# Sheet2.net
KiCad netlist of a schematic drawn in Altium Designer
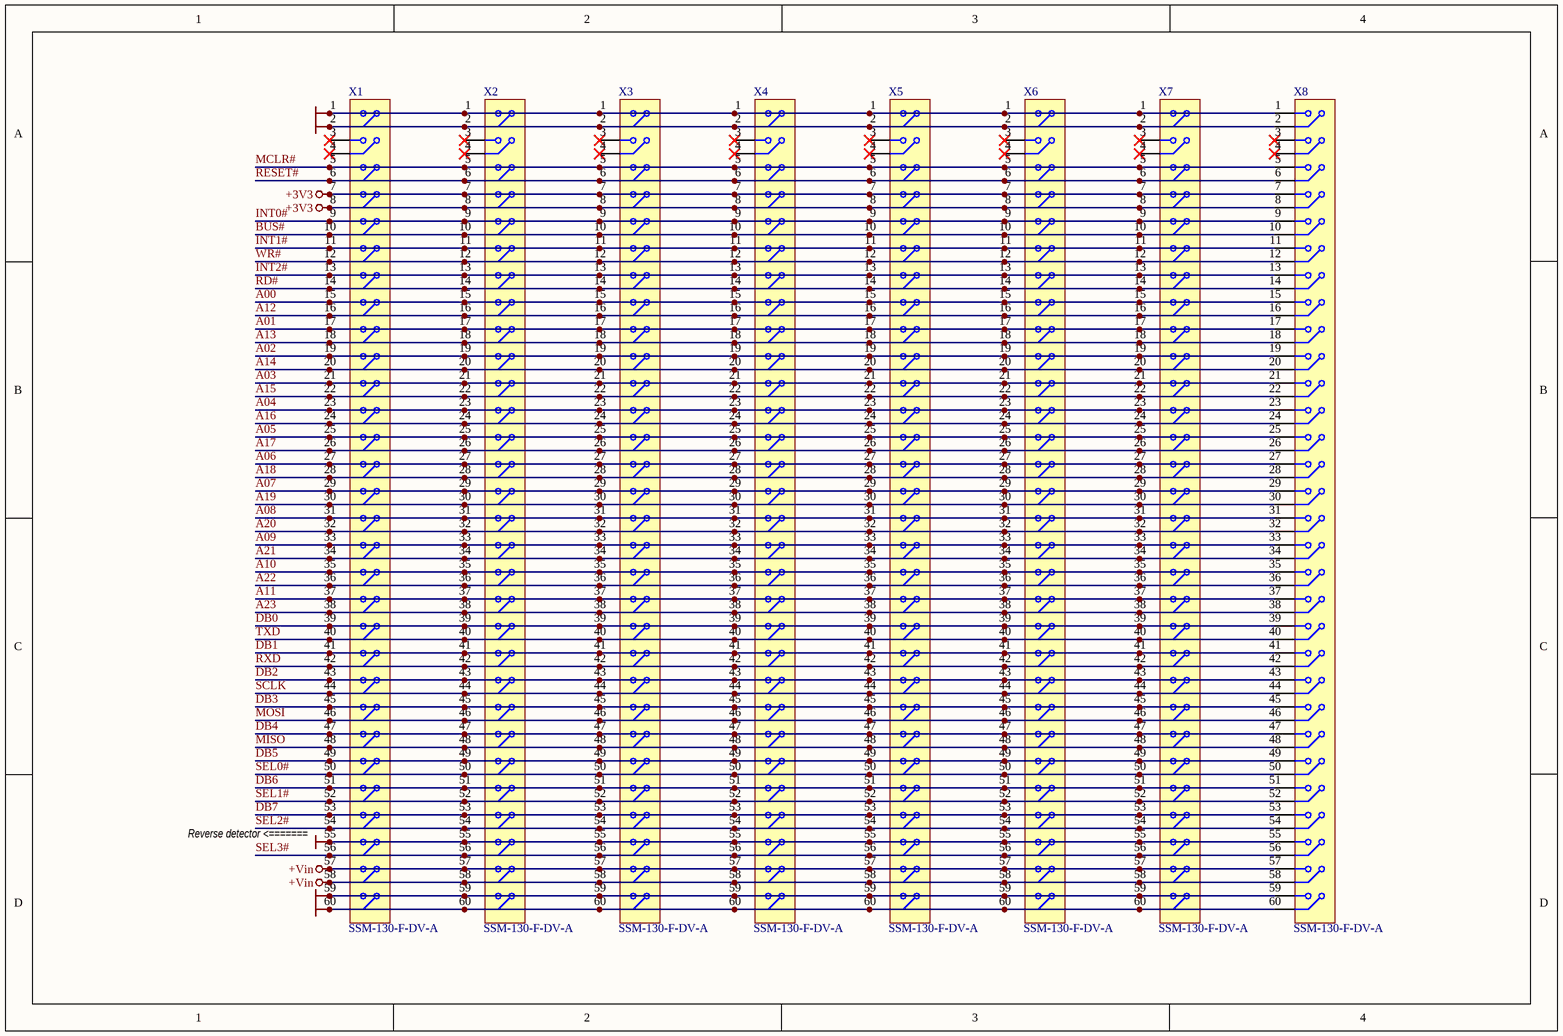
[diagram p0: Sheet2.SchDoc]

(export (version "E")
  (design (tool "Eeschema 10.0.6"))
  (components
    (comp (ref "X1")
      (value "SSM-130-F-DV-A")
      (footprint "2015-2X30XD")
      (description "Dual row, 60-way connector")
      (libsource (lib "Connectors") (part "Connector 2x30"))
    )
    (comp (ref "X2")
      (value "SSM-130-F-DV-A")
      (footprint "2015-2X30XD")
      (description "Dual row, 60-way connector")
      (libsource (lib "Connectors") (part "Connector 2x30"))
    )
    (comp (ref "X3")
      (value "SSM-130-F-DV-A")
      (footprint "2015-2X30XD")
      (description "Dual row, 60-way connector")
      (libsource (lib "Connectors") (part "Connector 2x30"))
    )
    (comp (ref "X4")
      (value "SSM-130-F-DV-A")
      (footprint "2015-2X30XD")
      (description "Dual row, 60-way connector")
      (libsource (lib "Connectors") (part "Connector 2x30"))
    )
    (comp (ref "X5")
      (value "SSM-130-F-DV-A")
      (footprint "2015-2X30XD")
      (description "Dual row, 60-way connector")
      (libsource (lib "Connectors") (part "Connector 2x30"))
    )
    (comp (ref "X6")
      (value "SSM-130-F-DV-A")
      (footprint "2015-2X30XD")
      (description "Dual row, 60-way connector")
      (libsource (lib "Connectors") (part "Connector 2x30"))
    )
    (comp (ref "X7")
      (value "SSM-130-F-DV-A")
      (footprint "2015-2X30XD")
      (description "Dual row, 60-way connector")
      (libsource (lib "Connectors") (part "Connector 2x30"))
    )
    (comp (ref "X8")
      (value "SSM-130-F-DV-A")
      (footprint "2015-2X30XD")
      (description "Dual row, 60-way connector")
      (libsource (lib "Connectors") (part "Connector 2x30"))
    )
  )
  (nets
    (net (code "1") (name "+3V3") (class "Default")
      (node (ref "X1") (pin "7") (pinfunction "7_7") (pintype "passive"))
      (node (ref "X1") (pin "8") (pinfunction "8_8") (pintype "passive"))
      (node (ref "X2") (pin "7") (pinfunction "7_7") (pintype "passive"))
      (node (ref "X2") (pin "8") (pinfunction "8_8") (pintype "passive"))
      (node (ref "X3") (pin "7") (pinfunction "7_7") (pintype "passive"))
      (node (ref "X3") (pin "8") (pinfunction "8_8") (pintype "passive"))
      (node (ref "X4") (pin "7") (pinfunction "7_7") (pintype "passive"))
      (node (ref "X4") (pin "8") (pinfunction "8_8") (pintype "passive"))
      (node (ref "X5") (pin "7") (pinfunction "7_7") (pintype "passive"))
      (node (ref "X5") (pin "8") (pinfunction "8_8") (pintype "passive"))
      (node (ref "X6") (pin "7") (pinfunction "7_7") (pintype "passive"))
      (node (ref "X6") (pin "8") (pinfunction "8_8") (pintype "passive"))
      (node (ref "X7") (pin "7") (pinfunction "7_7") (pintype "passive"))
      (node (ref "X7") (pin "8") (pinfunction "8_8") (pintype "passive"))
      (node (ref "X8") (pin "7") (pinfunction "7_7") (pintype "passive"))
      (node (ref "X8") (pin "8") (pinfunction "8_8") (pintype "passive"))
    )
    (net (code "2") (name "+Vin") (class "Default")
      (node (ref "X1") (pin "57") (pinfunction "57_57") (pintype "passive"))
      (node (ref "X1") (pin "58") (pinfunction "58_58") (pintype "passive"))
      (node (ref "X2") (pin "57") (pinfunction "57_57") (pintype "passive"))
      (node (ref "X2") (pin "58") (pinfunction "58_58") (pintype "passive"))
      (node (ref "X3") (pin "57") (pinfunction "57_57") (pintype "passive"))
      (node (ref "X3") (pin "58") (pinfunction "58_58") (pintype "passive"))
      (node (ref "X4") (pin "57") (pinfunction "57_57") (pintype "passive"))
      (node (ref "X4") (pin "58") (pinfunction "58_58") (pintype "passive"))
      (node (ref "X5") (pin "57") (pinfunction "57_57") (pintype "passive"))
      (node (ref "X5") (pin "58") (pinfunction "58_58") (pintype "passive"))
      (node (ref "X6") (pin "57") (pinfunction "57_57") (pintype "passive"))
      (node (ref "X6") (pin "58") (pinfunction "58_58") (pintype "passive"))
      (node (ref "X7") (pin "57") (pinfunction "57_57") (pintype "passive"))
      (node (ref "X7") (pin "58") (pinfunction "58_58") (pintype "passive"))
      (node (ref "X8") (pin "57") (pinfunction "57_57") (pintype "passive"))
      (node (ref "X8") (pin "58") (pinfunction "58_58") (pintype "passive"))
    )
    (net (code "3") (name "/A00") (class "Default")
      (node (ref "X1") (pin "15") (pinfunction "15_15") (pintype "passive"))
      (node (ref "X2") (pin "15") (pinfunction "15_15") (pintype "passive"))
      (node (ref "X3") (pin "15") (pinfunction "15_15") (pintype "passive"))
      (node (ref "X4") (pin "15") (pinfunction "15_15") (pintype "passive"))
      (node (ref "X5") (pin "15") (pinfunction "15_15") (pintype "passive"))
      (node (ref "X6") (pin "15") (pinfunction "15_15") (pintype "passive"))
      (node (ref "X7") (pin "15") (pinfunction "15_15") (pintype "passive"))
      (node (ref "X8") (pin "15") (pinfunction "15_15") (pintype "passive"))
    )
    (net (code "4") (name "/A01") (class "Default")
      (node (ref "X1") (pin "17") (pinfunction "17_17") (pintype "passive"))
      (node (ref "X2") (pin "17") (pinfunction "17_17") (pintype "passive"))
      (node (ref "X3") (pin "17") (pinfunction "17_17") (pintype "passive"))
      (node (ref "X4") (pin "17") (pinfunction "17_17") (pintype "passive"))
      (node (ref "X5") (pin "17") (pinfunction "17_17") (pintype "passive"))
      (node (ref "X6") (pin "17") (pinfunction "17_17") (pintype "passive"))
      (node (ref "X7") (pin "17") (pinfunction "17_17") (pintype "passive"))
      (node (ref "X8") (pin "17") (pinfunction "17_17") (pintype "passive"))
    )
    (net (code "5") (name "/A02") (class "Default")
      (node (ref "X1") (pin "19") (pinfunction "19_19") (pintype "passive"))
      (node (ref "X2") (pin "19") (pinfunction "19_19") (pintype "passive"))
      (node (ref "X3") (pin "19") (pinfunction "19_19") (pintype "passive"))
      (node (ref "X4") (pin "19") (pinfunction "19_19") (pintype "passive"))
      (node (ref "X5") (pin "19") (pinfunction "19_19") (pintype "passive"))
      (node (ref "X6") (pin "19") (pinfunction "19_19") (pintype "passive"))
      (node (ref "X7") (pin "19") (pinfunction "19_19") (pintype "passive"))
      (node (ref "X8") (pin "19") (pinfunction "19_19") (pintype "passive"))
    )
    (net (code "6") (name "/A03") (class "Default")
      (node (ref "X1") (pin "21") (pinfunction "21_21") (pintype "passive"))
      (node (ref "X2") (pin "21") (pinfunction "21_21") (pintype "passive"))
      (node (ref "X3") (pin "21") (pinfunction "21_21") (pintype "passive"))
      (node (ref "X4") (pin "21") (pinfunction "21_21") (pintype "passive"))
      (node (ref "X5") (pin "21") (pinfunction "21_21") (pintype "passive"))
      (node (ref "X6") (pin "21") (pinfunction "21_21") (pintype "passive"))
      (node (ref "X7") (pin "21") (pinfunction "21_21") (pintype "passive"))
      (node (ref "X8") (pin "21") (pinfunction "21_21") (pintype "passive"))
    )
    (net (code "7") (name "/A04") (class "Default")
      (node (ref "X1") (pin "23") (pinfunction "23_23") (pintype "passive"))
      (node (ref "X2") (pin "23") (pinfunction "23_23") (pintype "passive"))
      (node (ref "X3") (pin "23") (pinfunction "23_23") (pintype "passive"))
      (node (ref "X4") (pin "23") (pinfunction "23_23") (pintype "passive"))
      (node (ref "X5") (pin "23") (pinfunction "23_23") (pintype "passive"))
      (node (ref "X6") (pin "23") (pinfunction "23_23") (pintype "passive"))
      (node (ref "X7") (pin "23") (pinfunction "23_23") (pintype "passive"))
      (node (ref "X8") (pin "23") (pinfunction "23_23") (pintype "passive"))
    )
    (net (code "8") (name "/A05") (class "Default")
      (node (ref "X1") (pin "25") (pinfunction "25_25") (pintype "passive"))
      (node (ref "X2") (pin "25") (pinfunction "25_25") (pintype "passive"))
      (node (ref "X3") (pin "25") (pinfunction "25_25") (pintype "passive"))
      (node (ref "X4") (pin "25") (pinfunction "25_25") (pintype "passive"))
      (node (ref "X5") (pin "25") (pinfunction "25_25") (pintype "passive"))
      (node (ref "X6") (pin "25") (pinfunction "25_25") (pintype "passive"))
      (node (ref "X7") (pin "25") (pinfunction "25_25") (pintype "passive"))
      (node (ref "X8") (pin "25") (pinfunction "25_25") (pintype "passive"))
    )
    (net (code "9") (name "/A06") (class "Default")
      (node (ref "X1") (pin "27") (pinfunction "27_27") (pintype "passive"))
      (node (ref "X2") (pin "27") (pinfunction "27_27") (pintype "passive"))
      (node (ref "X3") (pin "27") (pinfunction "27_27") (pintype "passive"))
      (node (ref "X4") (pin "27") (pinfunction "27_27") (pintype "passive"))
      (node (ref "X5") (pin "27") (pinfunction "27_27") (pintype "passive"))
      (node (ref "X6") (pin "27") (pinfunction "27_27") (pintype "passive"))
      (node (ref "X7") (pin "27") (pinfunction "27_27") (pintype "passive"))
      (node (ref "X8") (pin "27") (pinfunction "27_27") (pintype "passive"))
    )
    (net (code "10") (name "/A07") (class "Default")
      (node (ref "X1") (pin "29") (pinfunction "29_29") (pintype "passive"))
      (node (ref "X2") (pin "29") (pinfunction "29_29") (pintype "passive"))
      (node (ref "X3") (pin "29") (pinfunction "29_29") (pintype "passive"))
      (node (ref "X4") (pin "29") (pinfunction "29_29") (pintype "passive"))
      (node (ref "X5") (pin "29") (pinfunction "29_29") (pintype "passive"))
      (node (ref "X6") (pin "29") (pinfunction "29_29") (pintype "passive"))
      (node (ref "X7") (pin "29") (pinfunction "29_29") (pintype "passive"))
      (node (ref "X8") (pin "29") (pinfunction "29_29") (pintype "passive"))
    )
    (net (code "11") (name "/A08") (class "Default")
      (node (ref "X1") (pin "31") (pinfunction "31_31") (pintype "passive"))
      (node (ref "X2") (pin "31") (pinfunction "31_31") (pintype "passive"))
      (node (ref "X3") (pin "31") (pinfunction "31_31") (pintype "passive"))
      (node (ref "X4") (pin "31") (pinfunction "31_31") (pintype "passive"))
      (node (ref "X5") (pin "31") (pinfunction "31_31") (pintype "passive"))
      (node (ref "X6") (pin "31") (pinfunction "31_31") (pintype "passive"))
      (node (ref "X7") (pin "31") (pinfunction "31_31") (pintype "passive"))
      (node (ref "X8") (pin "31") (pinfunction "31_31") (pintype "passive"))
    )
    (net (code "12") (name "/A09") (class "Default")
      (node (ref "X1") (pin "33") (pinfunction "33_33") (pintype "passive"))
      (node (ref "X2") (pin "33") (pinfunction "33_33") (pintype "passive"))
      (node (ref "X3") (pin "33") (pinfunction "33_33") (pintype "passive"))
      (node (ref "X4") (pin "33") (pinfunction "33_33") (pintype "passive"))
      (node (ref "X5") (pin "33") (pinfunction "33_33") (pintype "passive"))
      (node (ref "X6") (pin "33") (pinfunction "33_33") (pintype "passive"))
      (node (ref "X7") (pin "33") (pinfunction "33_33") (pintype "passive"))
      (node (ref "X8") (pin "33") (pinfunction "33_33") (pintype "passive"))
    )
    (net (code "13") (name "/A10") (class "Default")
      (node (ref "X1") (pin "35") (pinfunction "35_35") (pintype "passive"))
      (node (ref "X2") (pin "35") (pinfunction "35_35") (pintype "passive"))
      (node (ref "X3") (pin "35") (pinfunction "35_35") (pintype "passive"))
      (node (ref "X4") (pin "35") (pinfunction "35_35") (pintype "passive"))
      (node (ref "X5") (pin "35") (pinfunction "35_35") (pintype "passive"))
      (node (ref "X6") (pin "35") (pinfunction "35_35") (pintype "passive"))
      (node (ref "X7") (pin "35") (pinfunction "35_35") (pintype "passive"))
      (node (ref "X8") (pin "35") (pinfunction "35_35") (pintype "passive"))
    )
    (net (code "14") (name "/A11") (class "Default")
      (node (ref "X1") (pin "37") (pinfunction "37_37") (pintype "passive"))
      (node (ref "X2") (pin "37") (pinfunction "37_37") (pintype "passive"))
      (node (ref "X3") (pin "37") (pinfunction "37_37") (pintype "passive"))
      (node (ref "X4") (pin "37") (pinfunction "37_37") (pintype "passive"))
      (node (ref "X5") (pin "37") (pinfunction "37_37") (pintype "passive"))
      (node (ref "X6") (pin "37") (pinfunction "37_37") (pintype "passive"))
      (node (ref "X7") (pin "37") (pinfunction "37_37") (pintype "passive"))
      (node (ref "X8") (pin "37") (pinfunction "37_37") (pintype "passive"))
    )
    (net (code "15") (name "/A12") (class "Default")
      (node (ref "X1") (pin "16") (pinfunction "16_16") (pintype "passive"))
      (node (ref "X2") (pin "16") (pinfunction "16_16") (pintype "passive"))
      (node (ref "X3") (pin "16") (pinfunction "16_16") (pintype "passive"))
      (node (ref "X4") (pin "16") (pinfunction "16_16") (pintype "passive"))
      (node (ref "X5") (pin "16") (pinfunction "16_16") (pintype "passive"))
      (node (ref "X6") (pin "16") (pinfunction "16_16") (pintype "passive"))
      (node (ref "X7") (pin "16") (pinfunction "16_16") (pintype "passive"))
      (node (ref "X8") (pin "16") (pinfunction "16_16") (pintype "passive"))
    )
    (net (code "16") (name "/A13") (class "Default")
      (node (ref "X1") (pin "18") (pinfunction "18_18") (pintype "passive"))
      (node (ref "X2") (pin "18") (pinfunction "18_18") (pintype "passive"))
      (node (ref "X3") (pin "18") (pinfunction "18_18") (pintype "passive"))
      (node (ref "X4") (pin "18") (pinfunction "18_18") (pintype "passive"))
      (node (ref "X5") (pin "18") (pinfunction "18_18") (pintype "passive"))
      (node (ref "X6") (pin "18") (pinfunction "18_18") (pintype "passive"))
      (node (ref "X7") (pin "18") (pinfunction "18_18") (pintype "passive"))
      (node (ref "X8") (pin "18") (pinfunction "18_18") (pintype "passive"))
    )
    (net (code "17") (name "/A14") (class "Default")
      (node (ref "X1") (pin "20") (pinfunction "20_20") (pintype "passive"))
      (node (ref "X2") (pin "20") (pinfunction "20_20") (pintype "passive"))
      (node (ref "X3") (pin "20") (pinfunction "20_20") (pintype "passive"))
      (node (ref "X4") (pin "20") (pinfunction "20_20") (pintype "passive"))
      (node (ref "X5") (pin "20") (pinfunction "20_20") (pintype "passive"))
      (node (ref "X6") (pin "20") (pinfunction "20_20") (pintype "passive"))
      (node (ref "X7") (pin "20") (pinfunction "20_20") (pintype "passive"))
      (node (ref "X8") (pin "20") (pinfunction "20_20") (pintype "passive"))
    )
    (net (code "18") (name "/A15") (class "Default")
      (node (ref "X1") (pin "22") (pinfunction "22_22") (pintype "passive"))
      (node (ref "X2") (pin "22") (pinfunction "22_22") (pintype "passive"))
      (node (ref "X3") (pin "22") (pinfunction "22_22") (pintype "passive"))
      (node (ref "X4") (pin "22") (pinfunction "22_22") (pintype "passive"))
      (node (ref "X5") (pin "22") (pinfunction "22_22") (pintype "passive"))
      (node (ref "X6") (pin "22") (pinfunction "22_22") (pintype "passive"))
      (node (ref "X7") (pin "22") (pinfunction "22_22") (pintype "passive"))
      (node (ref "X8") (pin "22") (pinfunction "22_22") (pintype "passive"))
    )
    (net (code "19") (name "/A16") (class "Default")
      (node (ref "X1") (pin "24") (pinfunction "24_24") (pintype "passive"))
      (node (ref "X2") (pin "24") (pinfunction "24_24") (pintype "passive"))
      (node (ref "X3") (pin "24") (pinfunction "24_24") (pintype "passive"))
      (node (ref "X4") (pin "24") (pinfunction "24_24") (pintype "passive"))
      (node (ref "X5") (pin "24") (pinfunction "24_24") (pintype "passive"))
      (node (ref "X6") (pin "24") (pinfunction "24_24") (pintype "passive"))
      (node (ref "X7") (pin "24") (pinfunction "24_24") (pintype "passive"))
      (node (ref "X8") (pin "24") (pinfunction "24_24") (pintype "passive"))
    )
    (net (code "20") (name "/A17") (class "Default")
      (node (ref "X1") (pin "26") (pinfunction "26_26") (pintype "passive"))
      (node (ref "X2") (pin "26") (pinfunction "26_26") (pintype "passive"))
      (node (ref "X3") (pin "26") (pinfunction "26_26") (pintype "passive"))
      (node (ref "X4") (pin "26") (pinfunction "26_26") (pintype "passive"))
      (node (ref "X5") (pin "26") (pinfunction "26_26") (pintype "passive"))
      (node (ref "X6") (pin "26") (pinfunction "26_26") (pintype "passive"))
      (node (ref "X7") (pin "26") (pinfunction "26_26") (pintype "passive"))
      (node (ref "X8") (pin "26") (pinfunction "26_26") (pintype "passive"))
    )
    (net (code "21") (name "/A18") (class "Default")
      (node (ref "X1") (pin "28") (pinfunction "28_28") (pintype "passive"))
      (node (ref "X2") (pin "28") (pinfunction "28_28") (pintype "passive"))
      (node (ref "X3") (pin "28") (pinfunction "28_28") (pintype "passive"))
      (node (ref "X4") (pin "28") (pinfunction "28_28") (pintype "passive"))
      (node (ref "X5") (pin "28") (pinfunction "28_28") (pintype "passive"))
      (node (ref "X6") (pin "28") (pinfunction "28_28") (pintype "passive"))
      (node (ref "X7") (pin "28") (pinfunction "28_28") (pintype "passive"))
      (node (ref "X8") (pin "28") (pinfunction "28_28") (pintype "passive"))
    )
    (net (code "22") (name "/A19") (class "Default")
      (node (ref "X1") (pin "30") (pinfunction "30_30") (pintype "passive"))
      (node (ref "X2") (pin "30") (pinfunction "30_30") (pintype "passive"))
      (node (ref "X3") (pin "30") (pinfunction "30_30") (pintype "passive"))
      (node (ref "X4") (pin "30") (pinfunction "30_30") (pintype "passive"))
      (node (ref "X5") (pin "30") (pinfunction "30_30") (pintype "passive"))
      (node (ref "X6") (pin "30") (pinfunction "30_30") (pintype "passive"))
      (node (ref "X7") (pin "30") (pinfunction "30_30") (pintype "passive"))
      (node (ref "X8") (pin "30") (pinfunction "30_30") (pintype "passive"))
    )
    (net (code "23") (name "/A20") (class "Default")
      (node (ref "X1") (pin "32") (pinfunction "32_32") (pintype "passive"))
      (node (ref "X2") (pin "32") (pinfunction "32_32") (pintype "passive"))
      (node (ref "X3") (pin "32") (pinfunction "32_32") (pintype "passive"))
      (node (ref "X4") (pin "32") (pinfunction "32_32") (pintype "passive"))
      (node (ref "X5") (pin "32") (pinfunction "32_32") (pintype "passive"))
      (node (ref "X6") (pin "32") (pinfunction "32_32") (pintype "passive"))
      (node (ref "X7") (pin "32") (pinfunction "32_32") (pintype "passive"))
      (node (ref "X8") (pin "32") (pinfunction "32_32") (pintype "passive"))
    )
    (net (code "24") (name "/A21") (class "Default")
      (node (ref "X1") (pin "34") (pinfunction "34_34") (pintype "passive"))
      (node (ref "X2") (pin "34") (pinfunction "34_34") (pintype "passive"))
      (node (ref "X3") (pin "34") (pinfunction "34_34") (pintype "passive"))
      (node (ref "X4") (pin "34") (pinfunction "34_34") (pintype "passive"))
      (node (ref "X5") (pin "34") (pinfunction "34_34") (pintype "passive"))
      (node (ref "X6") (pin "34") (pinfunction "34_34") (pintype "passive"))
      (node (ref "X7") (pin "34") (pinfunction "34_34") (pintype "passive"))
      (node (ref "X8") (pin "34") (pinfunction "34_34") (pintype "passive"))
    )
    (net (code "25") (name "/A22") (class "Default")
      (node (ref "X1") (pin "36") (pinfunction "36_36") (pintype "passive"))
      (node (ref "X2") (pin "36") (pinfunction "36_36") (pintype "passive"))
      (node (ref "X3") (pin "36") (pinfunction "36_36") (pintype "passive"))
      (node (ref "X4") (pin "36") (pinfunction "36_36") (pintype "passive"))
      (node (ref "X5") (pin "36") (pinfunction "36_36") (pintype "passive"))
      (node (ref "X6") (pin "36") (pinfunction "36_36") (pintype "passive"))
      (node (ref "X7") (pin "36") (pinfunction "36_36") (pintype "passive"))
      (node (ref "X8") (pin "36") (pinfunction "36_36") (pintype "passive"))
    )
    (net (code "26") (name "/A23") (class "Default")
      (node (ref "X1") (pin "38") (pinfunction "38_38") (pintype "passive"))
      (node (ref "X2") (pin "38") (pinfunction "38_38") (pintype "passive"))
      (node (ref "X3") (pin "38") (pinfunction "38_38") (pintype "passive"))
      (node (ref "X4") (pin "38") (pinfunction "38_38") (pintype "passive"))
      (node (ref "X5") (pin "38") (pinfunction "38_38") (pintype "passive"))
      (node (ref "X6") (pin "38") (pinfunction "38_38") (pintype "passive"))
      (node (ref "X7") (pin "38") (pinfunction "38_38") (pintype "passive"))
      (node (ref "X8") (pin "38") (pinfunction "38_38") (pintype "passive"))
    )
    (net (code "27") (name "/BUS#") (class "Default")
      (node (ref "X1") (pin "10") (pinfunction "10_10") (pintype "passive"))
      (node (ref "X2") (pin "10") (pinfunction "10_10") (pintype "passive"))
      (node (ref "X3") (pin "10") (pinfunction "10_10") (pintype "passive"))
      (node (ref "X4") (pin "10") (pinfunction "10_10") (pintype "passive"))
      (node (ref "X5") (pin "10") (pinfunction "10_10") (pintype "passive"))
      (node (ref "X6") (pin "10") (pinfunction "10_10") (pintype "passive"))
      (node (ref "X7") (pin "10") (pinfunction "10_10") (pintype "passive"))
      (node (ref "X8") (pin "10") (pinfunction "10_10") (pintype "passive"))
    )
    (net (code "28") (name "/DB0") (class "Default")
      (node (ref "X1") (pin "39") (pinfunction "39_39") (pintype "passive"))
      (node (ref "X2") (pin "39") (pinfunction "39_39") (pintype "passive"))
      (node (ref "X3") (pin "39") (pinfunction "39_39") (pintype "passive"))
      (node (ref "X4") (pin "39") (pinfunction "39_39") (pintype "passive"))
      (node (ref "X5") (pin "39") (pinfunction "39_39") (pintype "passive"))
      (node (ref "X6") (pin "39") (pinfunction "39_39") (pintype "passive"))
      (node (ref "X7") (pin "39") (pinfunction "39_39") (pintype "passive"))
      (node (ref "X8") (pin "39") (pinfunction "39_39") (pintype "passive"))
    )
    (net (code "29") (name "/DB1") (class "Default")
      (node (ref "X1") (pin "41") (pinfunction "41_41") (pintype "passive"))
      (node (ref "X2") (pin "41") (pinfunction "41_41") (pintype "passive"))
      (node (ref "X3") (pin "41") (pinfunction "41_41") (pintype "passive"))
      (node (ref "X4") (pin "41") (pinfunction "41_41") (pintype "passive"))
      (node (ref "X5") (pin "41") (pinfunction "41_41") (pintype "passive"))
      (node (ref "X6") (pin "41") (pinfunction "41_41") (pintype "passive"))
      (node (ref "X7") (pin "41") (pinfunction "41_41") (pintype "passive"))
      (node (ref "X8") (pin "41") (pinfunction "41_41") (pintype "passive"))
    )
    (net (code "30") (name "/DB2") (class "Default")
      (node (ref "X1") (pin "43") (pinfunction "43_43") (pintype "passive"))
      (node (ref "X2") (pin "43") (pinfunction "43_43") (pintype "passive"))
      (node (ref "X3") (pin "43") (pinfunction "43_43") (pintype "passive"))
      (node (ref "X4") (pin "43") (pinfunction "43_43") (pintype "passive"))
      (node (ref "X5") (pin "43") (pinfunction "43_43") (pintype "passive"))
      (node (ref "X6") (pin "43") (pinfunction "43_43") (pintype "passive"))
      (node (ref "X7") (pin "43") (pinfunction "43_43") (pintype "passive"))
      (node (ref "X8") (pin "43") (pinfunction "43_43") (pintype "passive"))
    )
    (net (code "31") (name "/DB3") (class "Default")
      (node (ref "X1") (pin "45") (pinfunction "45_45") (pintype "passive"))
      (node (ref "X2") (pin "45") (pinfunction "45_45") (pintype "passive"))
      (node (ref "X3") (pin "45") (pinfunction "45_45") (pintype "passive"))
      (node (ref "X4") (pin "45") (pinfunction "45_45") (pintype "passive"))
      (node (ref "X5") (pin "45") (pinfunction "45_45") (pintype "passive"))
      (node (ref "X6") (pin "45") (pinfunction "45_45") (pintype "passive"))
      (node (ref "X7") (pin "45") (pinfunction "45_45") (pintype "passive"))
      (node (ref "X8") (pin "45") (pinfunction "45_45") (pintype "passive"))
    )
    (net (code "32") (name "/DB4") (class "Default")
      (node (ref "X1") (pin "47") (pinfunction "47_47") (pintype "passive"))
      (node (ref "X2") (pin "47") (pinfunction "47_47") (pintype "passive"))
      (node (ref "X3") (pin "47") (pinfunction "47_47") (pintype "passive"))
      (node (ref "X4") (pin "47") (pinfunction "47_47") (pintype "passive"))
      (node (ref "X5") (pin "47") (pinfunction "47_47") (pintype "passive"))
      (node (ref "X6") (pin "47") (pinfunction "47_47") (pintype "passive"))
      (node (ref "X7") (pin "47") (pinfunction "47_47") (pintype "passive"))
      (node (ref "X8") (pin "47") (pinfunction "47_47") (pintype "passive"))
    )
    (net (code "33") (name "/DB5") (class "Default")
      (node (ref "X1") (pin "49") (pinfunction "49_49") (pintype "passive"))
      (node (ref "X2") (pin "49") (pinfunction "49_49") (pintype "passive"))
      (node (ref "X3") (pin "49") (pinfunction "49_49") (pintype "passive"))
      (node (ref "X4") (pin "49") (pinfunction "49_49") (pintype "passive"))
      (node (ref "X5") (pin "49") (pinfunction "49_49") (pintype "passive"))
      (node (ref "X6") (pin "49") (pinfunction "49_49") (pintype "passive"))
      (node (ref "X7") (pin "49") (pinfunction "49_49") (pintype "passive"))
      (node (ref "X8") (pin "49") (pinfunction "49_49") (pintype "passive"))
    )
    (net (code "34") (name "/DB6") (class "Default")
      (node (ref "X1") (pin "51") (pinfunction "51_51") (pintype "passive"))
      (node (ref "X2") (pin "51") (pinfunction "51_51") (pintype "passive"))
      (node (ref "X3") (pin "51") (pinfunction "51_51") (pintype "passive"))
      (node (ref "X4") (pin "51") (pinfunction "51_51") (pintype "passive"))
      (node (ref "X5") (pin "51") (pinfunction "51_51") (pintype "passive"))
      (node (ref "X6") (pin "51") (pinfunction "51_51") (pintype "passive"))
      (node (ref "X7") (pin "51") (pinfunction "51_51") (pintype "passive"))
      (node (ref "X8") (pin "51") (pinfunction "51_51") (pintype "passive"))
    )
    (net (code "35") (name "/DB7") (class "Default")
      (node (ref "X1") (pin "53") (pinfunction "53_53") (pintype "passive"))
      (node (ref "X2") (pin "53") (pinfunction "53_53") (pintype "passive"))
      (node (ref "X3") (pin "53") (pinfunction "53_53") (pintype "passive"))
      (node (ref "X4") (pin "53") (pinfunction "53_53") (pintype "passive"))
      (node (ref "X5") (pin "53") (pinfunction "53_53") (pintype "passive"))
      (node (ref "X6") (pin "53") (pinfunction "53_53") (pintype "passive"))
      (node (ref "X7") (pin "53") (pinfunction "53_53") (pintype "passive"))
      (node (ref "X8") (pin "53") (pinfunction "53_53") (pintype "passive"))
    )
    (net (code "36") (name "/INT0#") (class "Default")
      (node (ref "X1") (pin "9") (pinfunction "9_9") (pintype "passive"))
      (node (ref "X2") (pin "9") (pinfunction "9_9") (pintype "passive"))
      (node (ref "X3") (pin "9") (pinfunction "9_9") (pintype "passive"))
      (node (ref "X4") (pin "9") (pinfunction "9_9") (pintype "passive"))
      (node (ref "X5") (pin "9") (pinfunction "9_9") (pintype "passive"))
      (node (ref "X6") (pin "9") (pinfunction "9_9") (pintype "passive"))
      (node (ref "X7") (pin "9") (pinfunction "9_9") (pintype "passive"))
      (node (ref "X8") (pin "9") (pinfunction "9_9") (pintype "passive"))
    )
    (net (code "37") (name "/INT1#") (class "Default")
      (node (ref "X1") (pin "11") (pinfunction "11_11") (pintype "passive"))
      (node (ref "X2") (pin "11") (pinfunction "11_11") (pintype "passive"))
      (node (ref "X3") (pin "11") (pinfunction "11_11") (pintype "passive"))
      (node (ref "X4") (pin "11") (pinfunction "11_11") (pintype "passive"))
      (node (ref "X5") (pin "11") (pinfunction "11_11") (pintype "passive"))
      (node (ref "X6") (pin "11") (pinfunction "11_11") (pintype "passive"))
      (node (ref "X7") (pin "11") (pinfunction "11_11") (pintype "passive"))
      (node (ref "X8") (pin "11") (pinfunction "11_11") (pintype "passive"))
    )
    (net (code "38") (name "/INT2#") (class "Default")
      (node (ref "X1") (pin "13") (pinfunction "13_13") (pintype "passive"))
      (node (ref "X2") (pin "13") (pinfunction "13_13") (pintype "passive"))
      (node (ref "X3") (pin "13") (pinfunction "13_13") (pintype "passive"))
      (node (ref "X4") (pin "13") (pinfunction "13_13") (pintype "passive"))
      (node (ref "X5") (pin "13") (pinfunction "13_13") (pintype "passive"))
      (node (ref "X6") (pin "13") (pinfunction "13_13") (pintype "passive"))
      (node (ref "X7") (pin "13") (pinfunction "13_13") (pintype "passive"))
      (node (ref "X8") (pin "13") (pinfunction "13_13") (pintype "passive"))
    )
    (net (code "39") (name "/MCLR#") (class "Default")
      (node (ref "X1") (pin "5") (pinfunction "5_5") (pintype "passive"))
      (node (ref "X2") (pin "5") (pinfunction "5_5") (pintype "passive"))
      (node (ref "X3") (pin "5") (pinfunction "5_5") (pintype "passive"))
      (node (ref "X4") (pin "5") (pinfunction "5_5") (pintype "passive"))
      (node (ref "X5") (pin "5") (pinfunction "5_5") (pintype "passive"))
      (node (ref "X6") (pin "5") (pinfunction "5_5") (pintype "passive"))
      (node (ref "X7") (pin "5") (pinfunction "5_5") (pintype "passive"))
      (node (ref "X8") (pin "5") (pinfunction "5_5") (pintype "passive"))
    )
    (net (code "40") (name "/MISO") (class "Default")
      (node (ref "X1") (pin "48") (pinfunction "48_48") (pintype "passive"))
      (node (ref "X2") (pin "48") (pinfunction "48_48") (pintype "passive"))
      (node (ref "X3") (pin "48") (pinfunction "48_48") (pintype "passive"))
      (node (ref "X4") (pin "48") (pinfunction "48_48") (pintype "passive"))
      (node (ref "X5") (pin "48") (pinfunction "48_48") (pintype "passive"))
      (node (ref "X6") (pin "48") (pinfunction "48_48") (pintype "passive"))
      (node (ref "X7") (pin "48") (pinfunction "48_48") (pintype "passive"))
      (node (ref "X8") (pin "48") (pinfunction "48_48") (pintype "passive"))
    )
    (net (code "41") (name "/MOSI") (class "Default")
      (node (ref "X1") (pin "46") (pinfunction "46_46") (pintype "passive"))
      (node (ref "X2") (pin "46") (pinfunction "46_46") (pintype "passive"))
      (node (ref "X3") (pin "46") (pinfunction "46_46") (pintype "passive"))
      (node (ref "X4") (pin "46") (pinfunction "46_46") (pintype "passive"))
      (node (ref "X5") (pin "46") (pinfunction "46_46") (pintype "passive"))
      (node (ref "X6") (pin "46") (pinfunction "46_46") (pintype "passive"))
      (node (ref "X7") (pin "46") (pinfunction "46_46") (pintype "passive"))
      (node (ref "X8") (pin "46") (pinfunction "46_46") (pintype "passive"))
    )
    (net (code "42") (name "/RD#") (class "Default")
      (node (ref "X1") (pin "14") (pinfunction "14_14") (pintype "passive"))
      (node (ref "X2") (pin "14") (pinfunction "14_14") (pintype "passive"))
      (node (ref "X3") (pin "14") (pinfunction "14_14") (pintype "passive"))
      (node (ref "X4") (pin "14") (pinfunction "14_14") (pintype "passive"))
      (node (ref "X5") (pin "14") (pinfunction "14_14") (pintype "passive"))
      (node (ref "X6") (pin "14") (pinfunction "14_14") (pintype "passive"))
      (node (ref "X7") (pin "14") (pinfunction "14_14") (pintype "passive"))
      (node (ref "X8") (pin "14") (pinfunction "14_14") (pintype "passive"))
    )
    (net (code "43") (name "/RESET#") (class "Default")
      (node (ref "X1") (pin "6") (pinfunction "6_6") (pintype "passive"))
      (node (ref "X2") (pin "6") (pinfunction "6_6") (pintype "passive"))
      (node (ref "X3") (pin "6") (pinfunction "6_6") (pintype "passive"))
      (node (ref "X4") (pin "6") (pinfunction "6_6") (pintype "passive"))
      (node (ref "X5") (pin "6") (pinfunction "6_6") (pintype "passive"))
      (node (ref "X6") (pin "6") (pinfunction "6_6") (pintype "passive"))
      (node (ref "X7") (pin "6") (pinfunction "6_6") (pintype "passive"))
      (node (ref "X8") (pin "6") (pinfunction "6_6") (pintype "passive"))
    )
    (net (code "44") (name "/RXD") (class "Default")
      (node (ref "X1") (pin "42") (pinfunction "42_42") (pintype "passive"))
      (node (ref "X2") (pin "42") (pinfunction "42_42") (pintype "passive"))
      (node (ref "X3") (pin "42") (pinfunction "42_42") (pintype "passive"))
      (node (ref "X4") (pin "42") (pinfunction "42_42") (pintype "passive"))
      (node (ref "X5") (pin "42") (pinfunction "42_42") (pintype "passive"))
      (node (ref "X6") (pin "42") (pinfunction "42_42") (pintype "passive"))
      (node (ref "X7") (pin "42") (pinfunction "42_42") (pintype "passive"))
      (node (ref "X8") (pin "42") (pinfunction "42_42") (pintype "passive"))
    )
    (net (code "45") (name "/SCLK") (class "Default")
      (node (ref "X1") (pin "44") (pinfunction "44_44") (pintype "passive"))
      (node (ref "X2") (pin "44") (pinfunction "44_44") (pintype "passive"))
      (node (ref "X3") (pin "44") (pinfunction "44_44") (pintype "passive"))
      (node (ref "X4") (pin "44") (pinfunction "44_44") (pintype "passive"))
      (node (ref "X5") (pin "44") (pinfunction "44_44") (pintype "passive"))
      (node (ref "X6") (pin "44") (pinfunction "44_44") (pintype "passive"))
      (node (ref "X7") (pin "44") (pinfunction "44_44") (pintype "passive"))
      (node (ref "X8") (pin "44") (pinfunction "44_44") (pintype "passive"))
    )
    (net (code "46") (name "/SEL0#") (class "Default")
      (node (ref "X1") (pin "50") (pinfunction "50_50") (pintype "passive"))
      (node (ref "X2") (pin "50") (pinfunction "50_50") (pintype "passive"))
      (node (ref "X3") (pin "50") (pinfunction "50_50") (pintype "passive"))
      (node (ref "X4") (pin "50") (pinfunction "50_50") (pintype "passive"))
      (node (ref "X5") (pin "50") (pinfunction "50_50") (pintype "passive"))
      (node (ref "X6") (pin "50") (pinfunction "50_50") (pintype "passive"))
      (node (ref "X7") (pin "50") (pinfunction "50_50") (pintype "passive"))
      (node (ref "X8") (pin "50") (pinfunction "50_50") (pintype "passive"))
    )
    (net (code "47") (name "/SEL1#") (class "Default")
      (node (ref "X1") (pin "52") (pinfunction "52_52") (pintype "passive"))
      (node (ref "X2") (pin "52") (pinfunction "52_52") (pintype "passive"))
      (node (ref "X3") (pin "52") (pinfunction "52_52") (pintype "passive"))
      (node (ref "X4") (pin "52") (pinfunction "52_52") (pintype "passive"))
      (node (ref "X5") (pin "52") (pinfunction "52_52") (pintype "passive"))
      (node (ref "X6") (pin "52") (pinfunction "52_52") (pintype "passive"))
      (node (ref "X7") (pin "52") (pinfunction "52_52") (pintype "passive"))
      (node (ref "X8") (pin "52") (pinfunction "52_52") (pintype "passive"))
    )
    (net (code "48") (name "/SEL2#") (class "Default")
      (node (ref "X1") (pin "54") (pinfunction "54_54") (pintype "passive"))
      (node (ref "X2") (pin "54") (pinfunction "54_54") (pintype "passive"))
      (node (ref "X3") (pin "54") (pinfunction "54_54") (pintype "passive"))
      (node (ref "X4") (pin "54") (pinfunction "54_54") (pintype "passive"))
      (node (ref "X5") (pin "54") (pinfunction "54_54") (pintype "passive"))
      (node (ref "X6") (pin "54") (pinfunction "54_54") (pintype "passive"))
      (node (ref "X7") (pin "54") (pinfunction "54_54") (pintype "passive"))
      (node (ref "X8") (pin "54") (pinfunction "54_54") (pintype "passive"))
    )
    (net (code "49") (name "/SEL3#") (class "Default")
      (node (ref "X1") (pin "56") (pinfunction "56_56") (pintype "passive"))
      (node (ref "X2") (pin "56") (pinfunction "56_56") (pintype "passive"))
      (node (ref "X3") (pin "56") (pinfunction "56_56") (pintype "passive"))
      (node (ref "X4") (pin "56") (pinfunction "56_56") (pintype "passive"))
      (node (ref "X5") (pin "56") (pinfunction "56_56") (pintype "passive"))
      (node (ref "X6") (pin "56") (pinfunction "56_56") (pintype "passive"))
      (node (ref "X7") (pin "56") (pinfunction "56_56") (pintype "passive"))
      (node (ref "X8") (pin "56") (pinfunction "56_56") (pintype "passive"))
    )
    (net (code "50") (name "/TXD") (class "Default")
      (node (ref "X1") (pin "40") (pinfunction "40_40") (pintype "passive"))
      (node (ref "X2") (pin "40") (pinfunction "40_40") (pintype "passive"))
      (node (ref "X3") (pin "40") (pinfunction "40_40") (pintype "passive"))
      (node (ref "X4") (pin "40") (pinfunction "40_40") (pintype "passive"))
      (node (ref "X5") (pin "40") (pinfunction "40_40") (pintype "passive"))
      (node (ref "X6") (pin "40") (pinfunction "40_40") (pintype "passive"))
      (node (ref "X7") (pin "40") (pinfunction "40_40") (pintype "passive"))
      (node (ref "X8") (pin "40") (pinfunction "40_40") (pintype "passive"))
    )
    (net (code "51") (name "/WR#") (class "Default")
      (node (ref "X1") (pin "12") (pinfunction "12_12") (pintype "passive"))
      (node (ref "X2") (pin "12") (pinfunction "12_12") (pintype "passive"))
      (node (ref "X3") (pin "12") (pinfunction "12_12") (pintype "passive"))
      (node (ref "X4") (pin "12") (pinfunction "12_12") (pintype "passive"))
      (node (ref "X5") (pin "12") (pinfunction "12_12") (pintype "passive"))
      (node (ref "X6") (pin "12") (pinfunction "12_12") (pintype "passive"))
      (node (ref "X7") (pin "12") (pinfunction "12_12") (pintype "passive"))
      (node (ref "X8") (pin "12") (pinfunction "12_12") (pintype "passive"))
    )
    (net (code "52") (name "GND") (class "Default")
      (node (ref "X1") (pin "1") (pinfunction "1_1") (pintype "passive"))
      (node (ref "X1") (pin "2") (pinfunction "2_2") (pintype "passive"))
      (node (ref "X1") (pin "55") (pinfunction "55_55") (pintype "passive"))
      (node (ref "X1") (pin "59") (pinfunction "59_59") (pintype "passive"))
      (node (ref "X1") (pin "60") (pinfunction "60_60") (pintype "passive"))
      (node (ref "X2") (pin "1") (pinfunction "1_1") (pintype "passive"))
      (node (ref "X2") (pin "2") (pinfunction "2_2") (pintype "passive"))
      (node (ref "X2") (pin "55") (pinfunction "55_55") (pintype "passive"))
      (node (ref "X2") (pin "59") (pinfunction "59_59") (pintype "passive"))
      (node (ref "X2") (pin "60") (pinfunction "60_60") (pintype "passive"))
      (node (ref "X3") (pin "1") (pinfunction "1_1") (pintype "passive"))
      (node (ref "X3") (pin "2") (pinfunction "2_2") (pintype "passive"))
      (node (ref "X3") (pin "55") (pinfunction "55_55") (pintype "passive"))
      (node (ref "X3") (pin "59") (pinfunction "59_59") (pintype "passive"))
      (node (ref "X3") (pin "60") (pinfunction "60_60") (pintype "passive"))
      (node (ref "X4") (pin "1") (pinfunction "1_1") (pintype "passive"))
      (node (ref "X4") (pin "2") (pinfunction "2_2") (pintype "passive"))
      (node (ref "X4") (pin "55") (pinfunction "55_55") (pintype "passive"))
      (node (ref "X4") (pin "59") (pinfunction "59_59") (pintype "passive"))
      (node (ref "X4") (pin "60") (pinfunction "60_60") (pintype "passive"))
      (node (ref "X5") (pin "1") (pinfunction "1_1") (pintype "passive"))
      (node (ref "X5") (pin "2") (pinfunction "2_2") (pintype "passive"))
      (node (ref "X5") (pin "55") (pinfunction "55_55") (pintype "passive"))
      (node (ref "X5") (pin "59") (pinfunction "59_59") (pintype "passive"))
      (node (ref "X5") (pin "60") (pinfunction "60_60") (pintype "passive"))
      (node (ref "X6") (pin "1") (pinfunction "1_1") (pintype "passive"))
      (node (ref "X6") (pin "2") (pinfunction "2_2") (pintype "passive"))
      (node (ref "X6") (pin "55") (pinfunction "55_55") (pintype "passive"))
      (node (ref "X6") (pin "59") (pinfunction "59_59") (pintype "passive"))
      (node (ref "X6") (pin "60") (pinfunction "60_60") (pintype "passive"))
      (node (ref "X7") (pin "1") (pinfunction "1_1") (pintype "passive"))
      (node (ref "X7") (pin "2") (pinfunction "2_2") (pintype "passive"))
      (node (ref "X7") (pin "55") (pinfunction "55_55") (pintype "passive"))
      (node (ref "X7") (pin "59") (pinfunction "59_59") (pintype "passive"))
      (node (ref "X7") (pin "60") (pinfunction "60_60") (pintype "passive"))
      (node (ref "X8") (pin "1") (pinfunction "1_1") (pintype "passive"))
      (node (ref "X8") (pin "2") (pinfunction "2_2") (pintype "passive"))
      (node (ref "X8") (pin "55") (pinfunction "55_55") (pintype "passive"))
      (node (ref "X8") (pin "59") (pinfunction "59_59") (pintype "passive"))
      (node (ref "X8") (pin "60") (pinfunction "60_60") (pintype "passive"))
    )
    (net (code "53") (name "unconnected-(X1-Pad3)") (class "Default")
      (node (ref "X1") (pin "3") (pinfunction "3_3") (pintype "passive+no_connect"))
    )
    (net (code "54") (name "unconnected-(X1-Pad4)") (class "Default")
      (node (ref "X1") (pin "4") (pinfunction "4_4") (pintype "passive+no_connect"))
    )
    (net (code "55") (name "unconnected-(X2-Pad3)") (class "Default")
      (node (ref "X2") (pin "3") (pinfunction "3_3") (pintype "passive+no_connect"))
    )
    (net (code "56") (name "unconnected-(X2-Pad4)") (class "Default")
      (node (ref "X2") (pin "4") (pinfunction "4_4") (pintype "passive+no_connect"))
    )
    (net (code "57") (name "unconnected-(X3-Pad3)") (class "Default")
      (node (ref "X3") (pin "3") (pinfunction "3_3") (pintype "passive+no_connect"))
    )
    (net (code "58") (name "unconnected-(X3-Pad4)") (class "Default")
      (node (ref "X3") (pin "4") (pinfunction "4_4") (pintype "passive+no_connect"))
    )
    (net (code "59") (name "unconnected-(X4-Pad3)") (class "Default")
      (node (ref "X4") (pin "3") (pinfunction "3_3") (pintype "passive+no_connect"))
    )
    (net (code "60") (name "unconnected-(X4-Pad4)") (class "Default")
      (node (ref "X4") (pin "4") (pinfunction "4_4") (pintype "passive+no_connect"))
    )
    (net (code "61") (name "unconnected-(X5-Pad3)") (class "Default")
      (node (ref "X5") (pin "3") (pinfunction "3_3") (pintype "passive+no_connect"))
    )
    (net (code "62") (name "unconnected-(X5-Pad4)") (class "Default")
      (node (ref "X5") (pin "4") (pinfunction "4_4") (pintype "passive+no_connect"))
    )
    (net (code "63") (name "unconnected-(X6-Pad3)") (class "Default")
      (node (ref "X6") (pin "3") (pinfunction "3_3") (pintype "passive+no_connect"))
    )
    (net (code "64") (name "unconnected-(X6-Pad4)") (class "Default")
      (node (ref "X6") (pin "4") (pinfunction "4_4") (pintype "passive+no_connect"))
    )
    (net (code "65") (name "unconnected-(X7-Pad3)") (class "Default")
      (node (ref "X7") (pin "3") (pinfunction "3_3") (pintype "passive+no_connect"))
    )
    (net (code "66") (name "unconnected-(X7-Pad4)") (class "Default")
      (node (ref "X7") (pin "4") (pinfunction "4_4") (pintype "passive+no_connect"))
    )
    (net (code "67") (name "unconnected-(X8-Pad3)") (class "Default")
      (node (ref "X8") (pin "3") (pinfunction "3_3") (pintype "passive+no_connect"))
    )
    (net (code "68") (name "unconnected-(X8-Pad4)") (class "Default")
      (node (ref "X8") (pin "4") (pinfunction "4_4") (pintype "passive+no_connect"))
    )
  )
)
